# SIX_OUTPORT-V2.net
KiCad netlist of a schematic drawn in Altium Designer
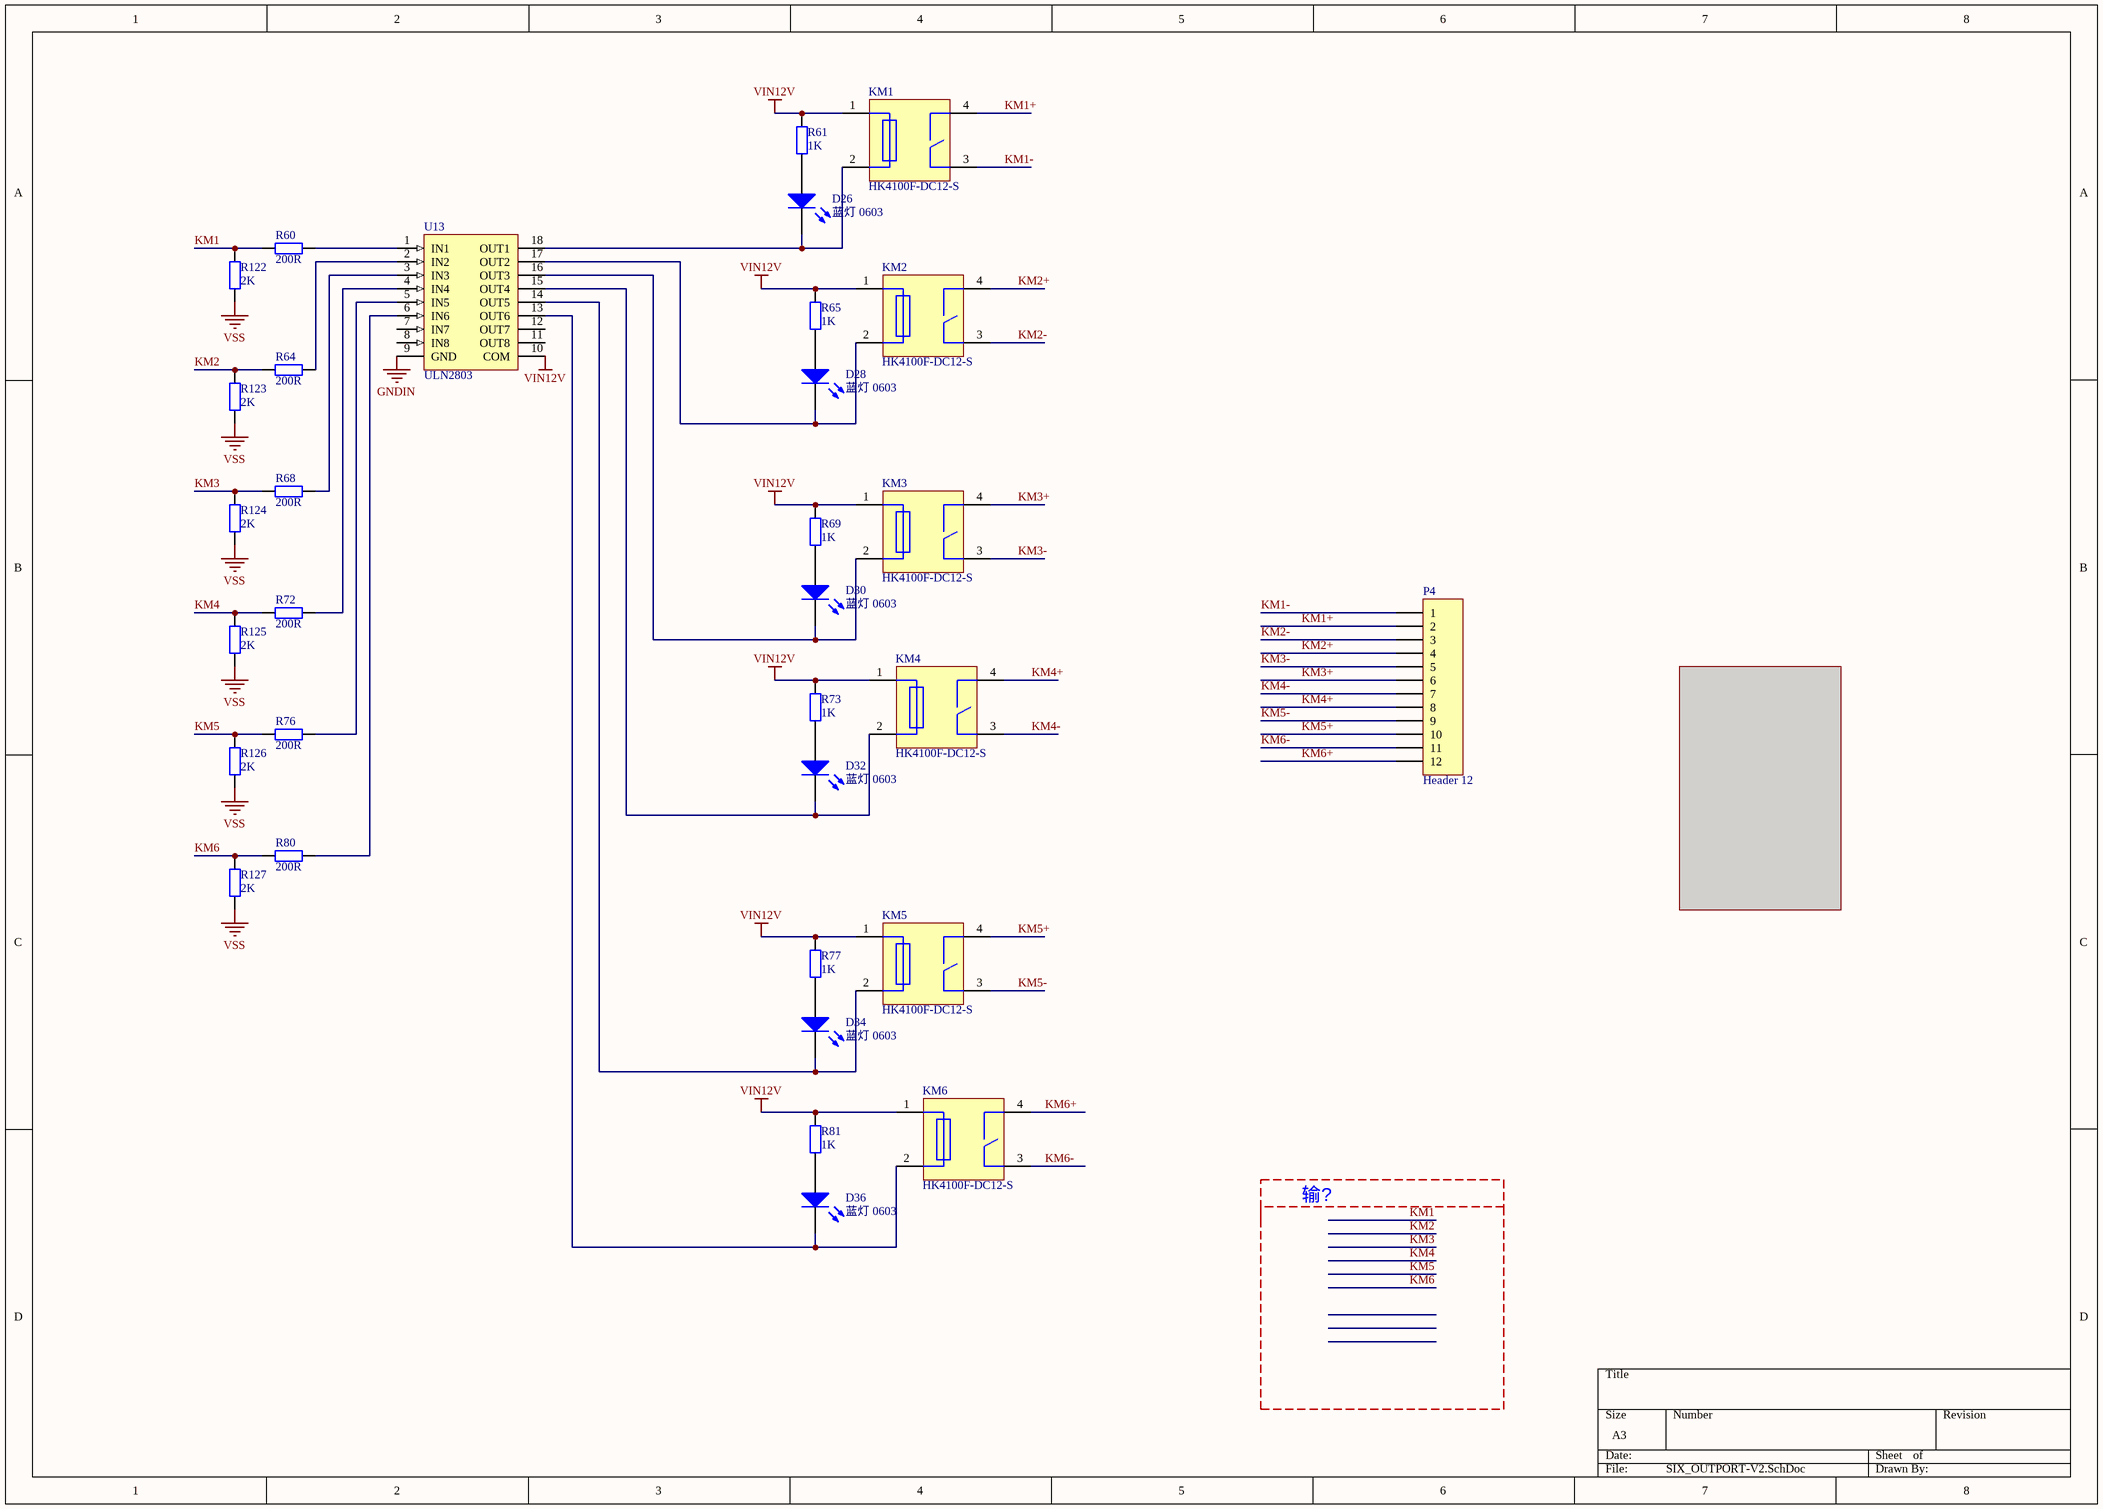
[diagram p0: SIX_OUTPORT-V2.SchDoc]

(export (version "E")
  (design (tool "Eeschema 10.0.6"))
  (components
    (comp (ref "D26")
      (value "蓝灯 0603")
      (footprint "LC-0603_LED_S1")
      (description "发光二极管")
      (libsource (lib "Miscellaneous Devices LC") (part "0603 蓝灯"))
    )
    (comp (ref "D28")
      (value "蓝灯 0603")
      (footprint "LC-0603_LED_S1")
      (description "发光二极管")
      (libsource (lib "Miscellaneous Devices LC") (part "0603 蓝灯"))
    )
    (comp (ref "D30")
      (value "蓝灯 0603")
      (footprint "LC-0603_LED_S1")
      (description "发光二极管")
      (libsource (lib "Miscellaneous Devices LC") (part "0603 蓝灯"))
    )
    (comp (ref "D32")
      (value "蓝灯 0603")
      (footprint "LC-0603_LED_S1")
      (description "发光二极管")
      (libsource (lib "Miscellaneous Devices LC") (part "0603 蓝灯"))
    )
    (comp (ref "D34")
      (value "蓝灯 0603")
      (footprint "LC-0603_LED_S1")
      (description "发光二极管")
      (libsource (lib "Miscellaneous Devices LC") (part "0603 蓝灯"))
    )
    (comp (ref "D36")
      (value "蓝灯 0603")
      (footprint "LC-0603_LED_S1")
      (description "发光二极管")
      (libsource (lib "Miscellaneous Devices LC") (part "0603 蓝灯"))
    )
    (comp (ref "KM1")
      (value "HK4100F-DC12-S")
      (footprint "JCZ-32F")
      (description "单刀双掷继电器")
      (libsource (lib "PCB_Project_2") (part "RELAY-HK4100F"))
    )
    (comp (ref "KM2")
      (value "HK4100F-DC12-S")
      (footprint "JCZ-32F")
      (description "单刀双掷继电器")
      (libsource (lib "PCB_Project_2") (part "RELAY-HK4100F"))
    )
    (comp (ref "KM3")
      (value "HK4100F-DC12-S")
      (footprint "JCZ-32F")
      (description "单刀双掷继电器")
      (libsource (lib "PCB_Project_2") (part "RELAY-HK4100F"))
    )
    (comp (ref "KM4")
      (value "HK4100F-DC12-S")
      (footprint "JCZ-32F")
      (description "单刀双掷继电器")
      (libsource (lib "PCB_Project_2") (part "RELAY-HK4100F"))
    )
    (comp (ref "KM5")
      (value "HK4100F-DC12-S")
      (footprint "JCZ-32F")
      (description "单刀双掷继电器")
      (libsource (lib "PCB_Project_2") (part "RELAY-HK4100F"))
    )
    (comp (ref "KM6")
      (value "HK4100F-DC12-S")
      (footprint "JCZ-32F")
      (description "单刀双掷继电器")
      (libsource (lib "PCB_Project_2") (part "RELAY-HK4100F"))
    )
    (comp (ref "P4")
      (value "Header 12")
      (footprint "F5.08-12P")
      (description "Header, 12-Pin")
      (fields (field (name "PUBLISHER") "Altium Limited"))
      (libsource (lib "Miscellaneous Connectors") (part "Header 12"))
    )
    (comp (ref "R60")
      (value "200R")
      (footprint "LC-0603_R")
      (description "Resistor")
      (fields (field (name "PUBLISHER") "Altium Limited"))
      (libsource (lib "Miscellaneous Devices") (part "Res2"))
    )
    (comp (ref "R61")
      (value "1K")
      (footprint "LC-0603_R")
      (description "Resistor")
      (fields (field (name "PUBLISHER") "Altium Limited"))
      (libsource (lib "") (part "Res2_1"))
    )
    (comp (ref "R64")
      (value "200R")
      (footprint "LC-0603_R")
      (description "Resistor")
      (fields (field (name "PUBLISHER") "Altium Limited"))
      (libsource (lib "Miscellaneous Devices") (part "Res2"))
    )
    (comp (ref "R65")
      (value "1K")
      (footprint "LC-0603_R")
      (description "Resistor")
      (fields (field (name "PUBLISHER") "Altium Limited"))
      (libsource (lib "") (part "Res2_1"))
    )
    (comp (ref "R68")
      (value "200R")
      (footprint "LC-0603_R")
      (description "Resistor")
      (fields (field (name "PUBLISHER") "Altium Limited"))
      (libsource (lib "Miscellaneous Devices") (part "Res2"))
    )
    (comp (ref "R69")
      (value "1K")
      (footprint "LC-0603_R")
      (description "Resistor")
      (fields (field (name "PUBLISHER") "Altium Limited"))
      (libsource (lib "") (part "Res2_1"))
    )
    (comp (ref "R72")
      (value "200R")
      (footprint "LC-0603_R")
      (description "Resistor")
      (fields (field (name "PUBLISHER") "Altium Limited"))
      (libsource (lib "Miscellaneous Devices") (part "Res2"))
    )
    (comp (ref "R73")
      (value "1K")
      (footprint "LC-0603_R")
      (description "Resistor")
      (fields (field (name "PUBLISHER") "Altium Limited"))
      (libsource (lib "") (part "Res2_1"))
    )
    (comp (ref "R76")
      (value "200R")
      (footprint "LC-0603_R")
      (description "Resistor")
      (fields (field (name "PUBLISHER") "Altium Limited"))
      (libsource (lib "Miscellaneous Devices") (part "Res2"))
    )
    (comp (ref "R77")
      (value "1K")
      (footprint "LC-0603_R")
      (description "Resistor")
      (fields (field (name "PUBLISHER") "Altium Limited"))
      (libsource (lib "") (part "Res2_1"))
    )
    (comp (ref "R80")
      (value "200R")
      (footprint "LC-0603_R")
      (description "Resistor")
      (fields (field (name "PUBLISHER") "Altium Limited"))
      (libsource (lib "Miscellaneous Devices") (part "Res2"))
    )
    (comp (ref "R81")
      (value "1K")
      (footprint "LC-0603_R")
      (description "Resistor")
      (fields (field (name "PUBLISHER") "Altium Limited"))
      (libsource (lib "") (part "Res2_1"))
    )
    (comp (ref "R122")
      (value "2K")
      (footprint "LC-0603_R")
      (description "Resistor")
      (fields (field (name "PUBLISHER") "Altium Limited"))
      (libsource (lib "") (part "Res2_1"))
    )
    (comp (ref "R123")
      (value "2K")
      (footprint "LC-0603_R")
      (description "Resistor")
      (fields (field (name "PUBLISHER") "Altium Limited"))
      (libsource (lib "") (part "Res2_1"))
    )
    (comp (ref "R124")
      (value "2K")
      (footprint "LC-0603_R")
      (description "Resistor")
      (fields (field (name "PUBLISHER") "Altium Limited"))
      (libsource (lib "") (part "Res2_1"))
    )
    (comp (ref "R125")
      (value "2K")
      (footprint "LC-0603_R")
      (description "Resistor")
      (fields (field (name "PUBLISHER") "Altium Limited"))
      (libsource (lib "") (part "Res2_1"))
    )
    (comp (ref "R126")
      (value "2K")
      (footprint "LC-0603_R")
      (description "Resistor")
      (fields (field (name "PUBLISHER") "Altium Limited"))
      (libsource (lib "") (part "Res2_1"))
    )
    (comp (ref "R127")
      (value "2K")
      (footprint "LC-0603_R")
      (description "Resistor")
      (fields (field (name "PUBLISHER") "Altium Limited"))
      (libsource (lib "") (part "Res2_1"))
    )
    (comp (ref "U13")
      (value "ULN2803")
      (footprint "LC-SOIC-18_300mil")
      (libsource (lib "SCH_Footp1_Lian") (part "ULN2803"))
    )
  )
  (nets
    (net (code "1") (name "/KM1") (class "Default")
      (node (ref "R122") (pin "1") (pinfunction "1_1") (pintype "passive"))
      (node (ref "R60") (pin "2") (pinfunction "2_2") (pintype "passive"))
    )
    (net (code "2") (name "/KM1+") (class "Default")
      (node (ref "KM1") (pin "4") (pinfunction "4_4") (pintype "passive"))
      (node (ref "P4") (pin "2") (pinfunction "2_2") (pintype "passive"))
    )
    (net (code "3") (name "/KM1-") (class "Default")
      (node (ref "KM1") (pin "3") (pinfunction "3_3") (pintype "passive"))
      (node (ref "P4") (pin "1") (pinfunction "1_1") (pintype "passive"))
    )
    (net (code "4") (name "/KM2") (class "Default")
      (node (ref "R123") (pin "1") (pinfunction "1_1") (pintype "passive"))
      (node (ref "R64") (pin "2") (pinfunction "2_2") (pintype "passive"))
    )
    (net (code "5") (name "/KM2+") (class "Default")
      (node (ref "KM2") (pin "4") (pinfunction "4_4") (pintype "passive"))
      (node (ref "P4") (pin "4") (pinfunction "4_4") (pintype "passive"))
    )
    (net (code "6") (name "/KM2-") (class "Default")
      (node (ref "KM2") (pin "3") (pinfunction "3_3") (pintype "passive"))
      (node (ref "P4") (pin "3") (pinfunction "3_3") (pintype "passive"))
    )
    (net (code "7") (name "/KM3") (class "Default")
      (node (ref "R124") (pin "1") (pinfunction "1_1") (pintype "passive"))
      (node (ref "R68") (pin "2") (pinfunction "2_2") (pintype "passive"))
    )
    (net (code "8") (name "/KM3+") (class "Default")
      (node (ref "KM3") (pin "4") (pinfunction "4_4") (pintype "passive"))
      (node (ref "P4") (pin "6") (pinfunction "6_6") (pintype "passive"))
    )
    (net (code "9") (name "/KM3-") (class "Default")
      (node (ref "KM3") (pin "3") (pinfunction "3_3") (pintype "passive"))
      (node (ref "P4") (pin "5") (pinfunction "5_5") (pintype "passive"))
    )
    (net (code "10") (name "/KM4") (class "Default")
      (node (ref "R125") (pin "1") (pinfunction "1_1") (pintype "passive"))
      (node (ref "R72") (pin "2") (pinfunction "2_2") (pintype "passive"))
    )
    (net (code "11") (name "/KM4+") (class "Default")
      (node (ref "KM4") (pin "4") (pinfunction "4_4") (pintype "passive"))
      (node (ref "P4") (pin "8") (pinfunction "8_8") (pintype "passive"))
    )
    (net (code "12") (name "/KM4-") (class "Default")
      (node (ref "KM4") (pin "3") (pinfunction "3_3") (pintype "passive"))
      (node (ref "P4") (pin "7") (pinfunction "7_7") (pintype "passive"))
    )
    (net (code "13") (name "/KM5") (class "Default")
      (node (ref "R126") (pin "1") (pinfunction "1_1") (pintype "passive"))
      (node (ref "R76") (pin "2") (pinfunction "2_2") (pintype "passive"))
    )
    (net (code "14") (name "/KM5+") (class "Default")
      (node (ref "KM5") (pin "4") (pinfunction "4_4") (pintype "passive"))
      (node (ref "P4") (pin "10") (pinfunction "10_10") (pintype "passive"))
    )
    (net (code "15") (name "/KM5-") (class "Default")
      (node (ref "KM5") (pin "3") (pinfunction "3_3") (pintype "passive"))
      (node (ref "P4") (pin "9") (pinfunction "9_9") (pintype "passive"))
    )
    (net (code "16") (name "/KM6") (class "Default")
      (node (ref "R127") (pin "1") (pinfunction "1_1") (pintype "passive"))
      (node (ref "R80") (pin "2") (pinfunction "2_2") (pintype "passive"))
    )
    (net (code "17") (name "/KM6+") (class "Default")
      (node (ref "KM6") (pin "4") (pinfunction "4_4") (pintype "passive"))
      (node (ref "P4") (pin "12") (pinfunction "12_12") (pintype "passive"))
    )
    (net (code "18") (name "/KM6-") (class "Default")
      (node (ref "KM6") (pin "3") (pinfunction "3_3") (pintype "passive"))
      (node (ref "P4") (pin "11") (pinfunction "11_11") (pintype "passive"))
    )
    (net (code "19") (name "GNDIN") (class "Default")
      (node (ref "U13") (pin "9") (pinfunction "GND_9") (pintype "power_in"))
    )
    (net (code "20") (name "Net-(D26-PadA)") (class "Default")
      (node (ref "D26") (pin "A") (pinfunction "A_A") (pintype "passive"))
      (node (ref "R61") (pin "2") (pinfunction "2_2") (pintype "passive"))
    )
    (net (code "21") (name "Net-(D28-PadA)") (class "Default")
      (node (ref "D28") (pin "A") (pinfunction "A_A") (pintype "passive"))
      (node (ref "R65") (pin "2") (pinfunction "2_2") (pintype "passive"))
    )
    (net (code "22") (name "Net-(D30-PadA)") (class "Default")
      (node (ref "D30") (pin "A") (pinfunction "A_A") (pintype "passive"))
      (node (ref "R69") (pin "2") (pinfunction "2_2") (pintype "passive"))
    )
    (net (code "23") (name "Net-(D32-PadA)") (class "Default")
      (node (ref "D32") (pin "A") (pinfunction "A_A") (pintype "passive"))
      (node (ref "R73") (pin "2") (pinfunction "2_2") (pintype "passive"))
    )
    (net (code "24") (name "Net-(D34-PadA)") (class "Default")
      (node (ref "D34") (pin "A") (pinfunction "A_A") (pintype "passive"))
      (node (ref "R77") (pin "2") (pinfunction "2_2") (pintype "passive"))
    )
    (net (code "25") (name "Net-(D36-PadA)") (class "Default")
      (node (ref "D36") (pin "A") (pinfunction "A_A") (pintype "passive"))
      (node (ref "R81") (pin "2") (pinfunction "2_2") (pintype "passive"))
    )
    (net (code "26") (name "Net-(U13-IN1)") (class "Default")
      (node (ref "R60") (pin "1") (pinfunction "1_1") (pintype "passive"))
      (node (ref "U13") (pin "1") (pinfunction "IN1_1") (pintype "input"))
    )
    (net (code "27") (name "Net-(U13-IN2)") (class "Default")
      (node (ref "R64") (pin "1") (pinfunction "1_1") (pintype "passive"))
      (node (ref "U13") (pin "2") (pinfunction "IN2_2") (pintype "input"))
    )
    (net (code "28") (name "Net-(U13-IN3)") (class "Default")
      (node (ref "R68") (pin "1") (pinfunction "1_1") (pintype "passive"))
      (node (ref "U13") (pin "3") (pinfunction "IN3_3") (pintype "input"))
    )
    (net (code "29") (name "Net-(U13-IN4)") (class "Default")
      (node (ref "R72") (pin "1") (pinfunction "1_1") (pintype "passive"))
      (node (ref "U13") (pin "4") (pinfunction "IN4_4") (pintype "input"))
    )
    (net (code "30") (name "Net-(U13-IN5)") (class "Default")
      (node (ref "R76") (pin "1") (pinfunction "1_1") (pintype "passive"))
      (node (ref "U13") (pin "5") (pinfunction "IN5_5") (pintype "input"))
    )
    (net (code "31") (name "Net-(U13-IN6)") (class "Default")
      (node (ref "R80") (pin "1") (pinfunction "1_1") (pintype "passive"))
      (node (ref "U13") (pin "6") (pinfunction "IN6_6") (pintype "input"))
    )
    (net (code "32") (name "Net-(U13-OUT1)") (class "Default")
      (node (ref "D26") (pin "K") (pinfunction "K_K") (pintype "passive"))
      (node (ref "KM1") (pin "2") (pinfunction "2_2") (pintype "passive"))
      (node (ref "U13") (pin "18") (pinfunction "OUT1_18") (pintype "open_collector"))
    )
    (net (code "33") (name "Net-(U13-OUT2)") (class "Default")
      (node (ref "D28") (pin "K") (pinfunction "K_K") (pintype "passive"))
      (node (ref "KM2") (pin "2") (pinfunction "2_2") (pintype "passive"))
      (node (ref "U13") (pin "17") (pinfunction "OUT2_17") (pintype "open_collector"))
    )
    (net (code "34") (name "Net-(U13-OUT3)") (class "Default")
      (node (ref "D30") (pin "K") (pinfunction "K_K") (pintype "passive"))
      (node (ref "KM3") (pin "2") (pinfunction "2_2") (pintype "passive"))
      (node (ref "U13") (pin "16") (pinfunction "OUT3_16") (pintype "open_collector"))
    )
    (net (code "35") (name "Net-(U13-OUT4)") (class "Default")
      (node (ref "D32") (pin "K") (pinfunction "K_K") (pintype "passive"))
      (node (ref "KM4") (pin "2") (pinfunction "2_2") (pintype "passive"))
      (node (ref "U13") (pin "15") (pinfunction "OUT4_15") (pintype "open_collector"))
    )
    (net (code "36") (name "Net-(U13-OUT5)") (class "Default")
      (node (ref "D34") (pin "K") (pinfunction "K_K") (pintype "passive"))
      (node (ref "KM5") (pin "2") (pinfunction "2_2") (pintype "passive"))
      (node (ref "U13") (pin "14") (pinfunction "OUT5_14") (pintype "open_collector"))
    )
    (net (code "37") (name "Net-(U13-OUT6)") (class "Default")
      (node (ref "D36") (pin "K") (pinfunction "K_K") (pintype "passive"))
      (node (ref "KM6") (pin "2") (pinfunction "2_2") (pintype "passive"))
      (node (ref "U13") (pin "13") (pinfunction "OUT6_13") (pintype "open_collector"))
    )
    (net (code "38") (name "VIN12V") (class "Default")
      (node (ref "KM1") (pin "1") (pinfunction "1_1") (pintype "passive"))
      (node (ref "KM2") (pin "1") (pinfunction "1_1") (pintype "passive"))
      (node (ref "KM3") (pin "1") (pinfunction "1_1") (pintype "passive"))
      (node (ref "KM4") (pin "1") (pinfunction "1_1") (pintype "passive"))
      (node (ref "KM5") (pin "1") (pinfunction "1_1") (pintype "passive"))
      (node (ref "KM6") (pin "1") (pinfunction "1_1") (pintype "passive"))
      (node (ref "R61") (pin "1") (pinfunction "1_1") (pintype "passive"))
      (node (ref "R65") (pin "1") (pinfunction "1_1") (pintype "passive"))
      (node (ref "R69") (pin "1") (pinfunction "1_1") (pintype "passive"))
      (node (ref "R73") (pin "1") (pinfunction "1_1") (pintype "passive"))
      (node (ref "R77") (pin "1") (pinfunction "1_1") (pintype "passive"))
      (node (ref "R81") (pin "1") (pinfunction "1_1") (pintype "passive"))
      (node (ref "U13") (pin "10") (pinfunction "COM_10") (pintype "passive"))
    )
    (net (code "39") (name "VSS") (class "Default")
      (node (ref "R122") (pin "2") (pinfunction "2_2") (pintype "passive"))
      (node (ref "R123") (pin "2") (pinfunction "2_2") (pintype "passive"))
      (node (ref "R124") (pin "2") (pinfunction "2_2") (pintype "passive"))
      (node (ref "R125") (pin "2") (pinfunction "2_2") (pintype "passive"))
      (node (ref "R126") (pin "2") (pinfunction "2_2") (pintype "passive"))
      (node (ref "R127") (pin "2") (pinfunction "2_2") (pintype "passive"))
    )
    (net (code "40") (name "unconnected-(U13-IN7-Pad7)") (class "Default")
      (node (ref "U13") (pin "7") (pinfunction "IN7_7") (pintype "input"))
    )
    (net (code "41") (name "unconnected-(U13-IN8-Pad8)") (class "Default")
      (node (ref "U13") (pin "8") (pinfunction "IN8_8") (pintype "input"))
    )
    (net (code "42") (name "unconnected-(U13-OUT7-Pad12)") (class "Default")
      (node (ref "U13") (pin "12") (pinfunction "OUT7_12") (pintype "open_collector"))
    )
    (net (code "43") (name "unconnected-(U13-OUT8-Pad11)") (class "Default")
      (node (ref "U13") (pin "11") (pinfunction "OUT8_11") (pintype "passive"))
    )
  )
)
